# TSAL-S01-V00-Control.net
KiCad netlist of a schematic drawn in Altium Designer
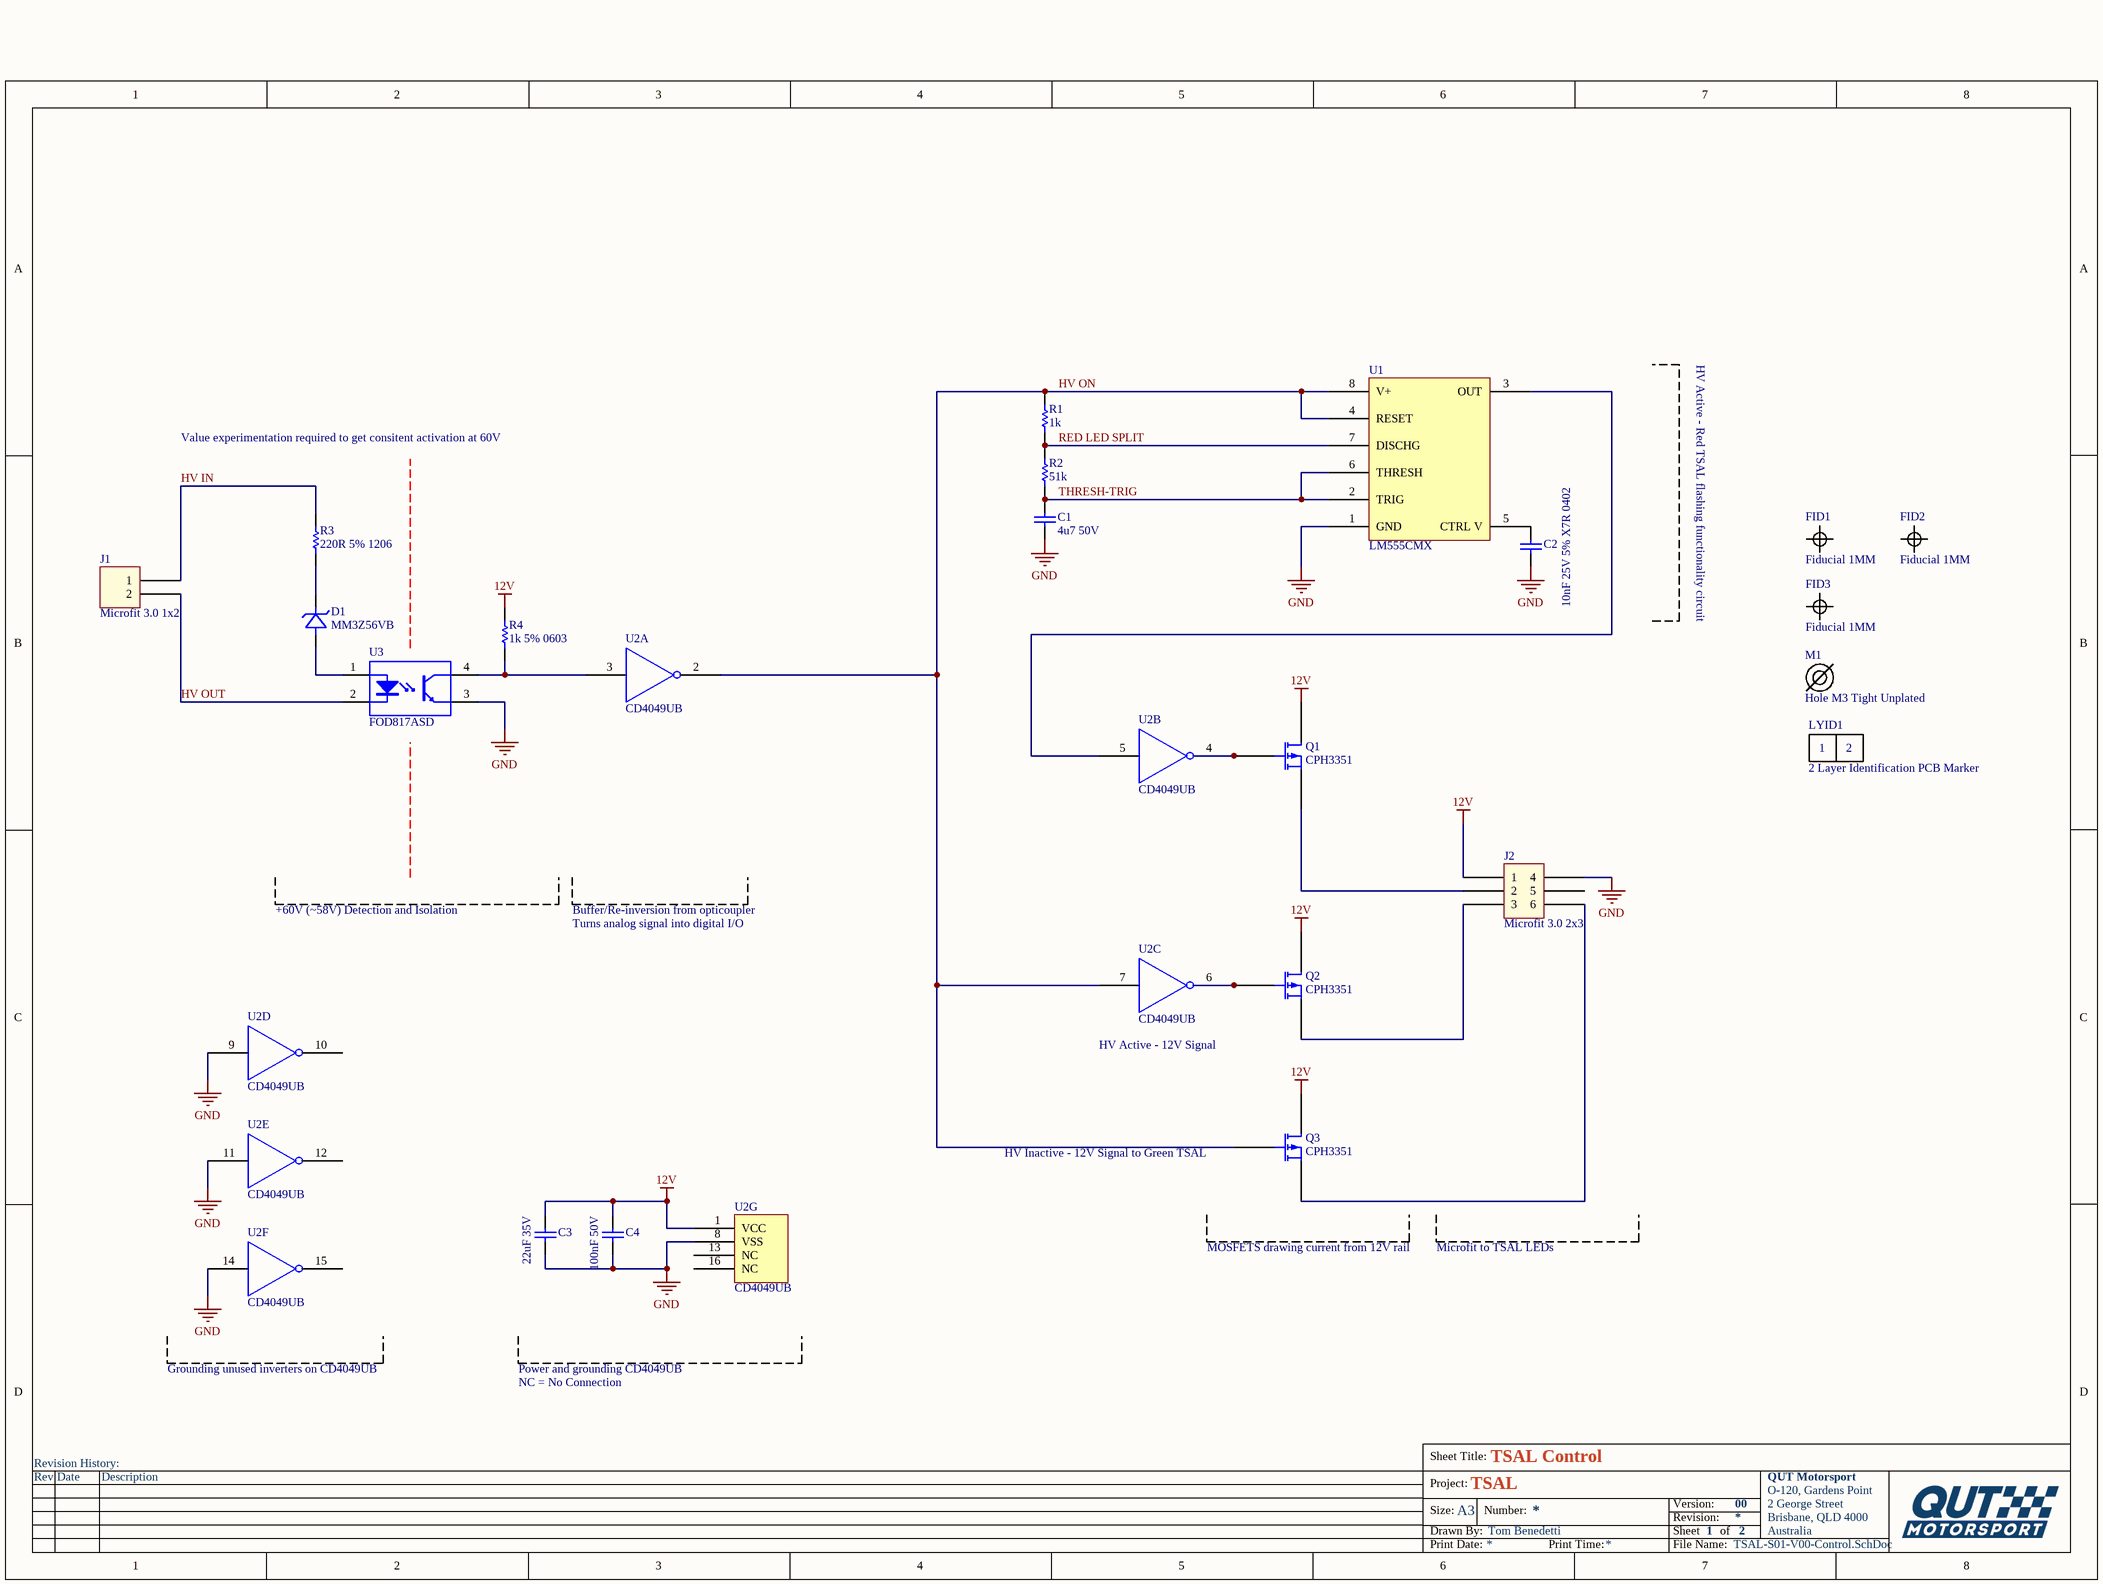
[diagram p0: TSAL-S01-V00-Control.SchDoc]

(export (version "E")
  (design (tool "Eeschema 10.0.6"))
  (components
    (comp (ref "C1")
      (value "4u7 50V")
      (footprint "Cap_Ceramic_0603")
      (description "Capacitor, Ceramic, SMD, 4u7, 50V, 5%, X7R, 0603")
      (libsource (lib "StandardCapacitors") (part "4u7 50V 5% X7R 0603"))
    )
    (comp (ref "C2")
      (value "10nF 25V 5% X7R 0402")
      (footprint "Cap_Ceramic_1206")
      (description "10000pF ±5% 25V Ceramic Capacitor X7R 0402 (1005 Metric)")
      (libsource (lib "StandardCapacitors") (part "10nF 25V 5% X7R 0402"))
    )
    (comp (ref "C3")
      (value "22uF 35V")
      (footprint "Cap_Ceramic_1206")
      (description "22µF ±20% 35V Ceramic Capacitor X5R 1206 (3216 Metric)")
      (libsource (lib "StandardCapacitors") (part "22uF 35V 20% X5R 1206"))
    )
    (comp (ref "C4")
      (value "100nF 50V")
      (footprint "Cap_Ceramic_0603")
      (description "Capacitor, Ceramic, SMD, 100nF, 50V, 5%, X7R, 0603")
      (libsource (lib "StandardCapacitors") (part "100nF 50V 5% X7R 0603"))
    )
    (comp (ref "D1")
      (value "MM3Z56VB")
      (footprint "SOD-323F")
      (description "Zener Diode 56V 200mW ±2% Surface Mount SOD-323F")
      (fields (field (name "MANUFACTURER") "ON Semiconductor"))
      (libsource (lib "QUTMS_DiodeLibrary") (part "MM3Z56VB"))
    )
    (comp (ref "FID1")
      (value "Fiducial 1MM")
      (footprint "FIDUCIAL 1MM")
      (libsource (lib "QUTMS_PCBLibrary") (part "Fiducial 1MM"))
    )
    (comp (ref "FID2")
      (value "Fiducial 1MM")
      (footprint "FIDUCIAL 1MM")
      (libsource (lib "QUTMS_PCBLibrary") (part "Fiducial 1MM"))
    )
    (comp (ref "FID3")
      (value "Fiducial 1MM")
      (footprint "FIDUCIAL 1MM")
      (libsource (lib "QUTMS_PCBLibrary") (part "Fiducial 1MM"))
    )
    (comp (ref "J1")
      (value "Microfit 3.0 1x2")
      (footprint "Microfit_1X2_R_TH")
      (libsource (lib "QUTMS_MicrofitLibrary") (part "Microfit_1x2"))
    )
    (comp (ref "J2")
      (value "Microfit 3.0 2x3")
      (footprint "Microfit_2X3_R_TH")
      (libsource (lib "QUTMS_MicrofitLibrary") (part "Microfit_2x3"))
    )
    (comp (ref "LYID1")
      (value "2 Layer Identification PCB Marker")
      (footprint "LAYER IDENT 2")
      (libsource (lib "QUTMS_PCBLibrary") (part "Layer Identification 2"))
    )
    (comp (ref "M1")
      (value "Hole M3 Tight Unplated")
      (footprint "M3.2 UNPLATED")
      (description "M3.2 Hole, No Plating")
      (libsource (lib "QUTMS_PCBLibrary") (part "Hole M3 Tight Unplated"))
    )
    (comp (ref "Q1")
      (value "CPH3351")
      (footprint "SOT-23-3")
      (description "P-Channel 60V 1.8A (Ta) 1W (Ta) Surface Mount 3-CPH")
      (libsource (lib "QUTMS_Transistors") (part "CPH3351"))
    )
    (comp (ref "Q2")
      (value "CPH3351")
      (footprint "SOT-23-3")
      (description "P-Channel 60V 1.8A (Ta) 1W (Ta) Surface Mount 3-CPH")
      (libsource (lib "QUTMS_Transistors") (part "CPH3351"))
    )
    (comp (ref "Q3")
      (value "CPH3351")
      (footprint "SOT-23-3")
      (description "P-Channel 60V 1.8A (Ta) 1W (Ta) Surface Mount 3-CPH")
      (libsource (lib "QUTMS_Transistors") (part "CPH3351"))
    )
    (comp (ref "R1")
      (value "1k")
      (footprint "Res_ThinFilm_0603")
      (description "Resistor, SMD, 1k, 0.1W, 5%, 0603")
      (libsource (lib "StandardResistors") (part "1k 5% 0603"))
    )
    (comp (ref "R2")
      (value "51k")
      (footprint "Res_ThinFilm_0603")
      (description "51 kOhms ±0.1% 0.063W, 1/16W Chip Resistor 0402 (1005 Metric) Automotive AEC-Q200 Thin Film")
      (libsource (lib "StandardResistors") (part "51k 5% 0603"))
    )
    (comp (ref "R3")
      (value "220R 5% 1206")
      (footprint "Res_ThinFilm_1206")
      (description "220 Ohms ±1% 0.25W, 1/4W Chip Resistor 1206 (3216 Metric) Moisture Resistant Thick Film")
      (libsource (lib "StandardResistors") (part "220R 5% 1206"))
    )
    (comp (ref "R4")
      (value "1k 5% 0603")
      (footprint "Res_ThinFilm_0603")
      (description "Resistor, SMD, 1k, 0.1W, 5%, 0603")
      (libsource (lib "StandardResistors") (part "1k 5% 0603"))
    )
    (comp (ref "U1")
      (value "LM555CMX")
      (footprint "MCP2561 SOIC")
      (description "555 Type, Timer/Oscillator (Single) IC 100kHz 8-SOIC")
      (libsource (lib "QUTMS_IntegratedCircuitLibrary") (part "LM555CMX"))
    )
    (comp (ref "U2")
      (value "CD4049UB")
      (footprint "CD4049UB")
      (libsource (lib "QUTMS_LogicLibrary") (part "CD4049UB"))
    )
    (comp (ref "U3")
      (value "FOD817ASD")
      (footprint "FOD817ASD")
      (description "Optoisolator 5kV Transistor 4SMD")
      (libsource (lib "QUTMS_OctocouplerLibrary") (part "FOD817ASD"))
    )
  )
  (nets
    (net (code "1") (name "/HV IN") (class "Default")
      (node (ref "J1") (pin "1") (pinfunction "1_1") (pintype "passive"))
      (node (ref "R3") (pin "2") (pinfunction "2_2") (pintype "passive"))
    )
    (net (code "2") (name "/HV ON") (class "Default")
      (node (ref "Q3") (pin "G") (pinfunction "G_G") (pintype "passive"))
      (node (ref "R1") (pin "2") (pinfunction "2_2") (pintype "passive"))
      (node (ref "U1") (pin "4") (pinfunction "RESET_4") (pintype "passive"))
      (node (ref "U1") (pin "8") (pinfunction "V+_8") (pintype "passive"))
      (node (ref "U2") (pin "2") (pinfunction "G_2") (pintype "passive"))
      (node (ref "U2") (pin "7") (pinfunction "C_7") (pintype "passive"))
    )
    (net (code "3") (name "/HV OUT") (class "Default")
      (node (ref "J1") (pin "2") (pinfunction "2_2") (pintype "passive"))
      (node (ref "U3") (pin "2") (pinfunction "CATHODE_2") (pintype "passive"))
    )
    (net (code "4") (name "/RED LED SPLIT") (class "Default")
      (node (ref "R1") (pin "1") (pinfunction "1_1") (pintype "passive"))
      (node (ref "R2") (pin "2") (pinfunction "2_2") (pintype "passive"))
      (node (ref "U1") (pin "7") (pinfunction "DISCHG_7") (pintype "passive"))
    )
    (net (code "5") (name "/THRESH-TRIG") (class "Default")
      (node (ref "C1") (pin "2") (pinfunction "2_2") (pintype "passive"))
      (node (ref "R2") (pin "1") (pinfunction "1_1") (pintype "passive"))
      (node (ref "U1") (pin "2") (pinfunction "TRIG_2") (pintype "passive"))
      (node (ref "U1") (pin "6") (pinfunction "THRESH_6") (pintype "passive"))
    )
    (net (code "6") (name "12V") (class "Default")
      (node (ref "C3") (pin "2") (pinfunction "2_2") (pintype "passive"))
      (node (ref "C4") (pin "2") (pinfunction "2_2") (pintype "passive"))
      (node (ref "J2") (pin "1") (pinfunction "1_1") (pintype "passive"))
      (node (ref "Q1") (pin "D") (pinfunction "D_D") (pintype "passive"))
      (node (ref "Q2") (pin "D") (pinfunction "D_D") (pintype "passive"))
      (node (ref "Q3") (pin "D") (pinfunction "D_D") (pintype "passive"))
      (node (ref "R4") (pin "2") (pinfunction "2_2") (pintype "passive"))
      (node (ref "U2") (pin "1") (pinfunction "VCC_1") (pintype "passive"))
    )
    (net (code "7") (name "GND") (class "Default")
      (node (ref "C1") (pin "1") (pinfunction "1_1") (pintype "passive"))
      (node (ref "C2") (pin "1") (pinfunction "1_1") (pintype "passive"))
      (node (ref "C3") (pin "1") (pinfunction "1_1") (pintype "passive"))
      (node (ref "C4") (pin "1") (pinfunction "1_1") (pintype "passive"))
      (node (ref "J2") (pin "4") (pinfunction "4_4") (pintype "passive"))
      (node (ref "U1") (pin "1") (pinfunction "GND_1") (pintype "passive"))
      (node (ref "U2") (pin "11") (pinfunction "E_11") (pintype "passive"))
      (node (ref "U2") (pin "14") (pinfunction "F_14") (pintype "passive"))
      (node (ref "U2") (pin "8") (pinfunction "VSS_8") (pintype "passive"))
      (node (ref "U2") (pin "9") (pinfunction "D_9") (pintype "passive"))
      (node (ref "U3") (pin "3") (pinfunction "EMITTER_3") (pintype "passive"))
    )
    (net (code "8") (name "Net-(D1-Anode)") (class "Default")
      (node (ref "D1") (pin "1") (pinfunction "Anode_1") (pintype "passive"))
      (node (ref "U3") (pin "1") (pinfunction "ANODE_1") (pintype "passive"))
    )
    (net (code "9") (name "Net-(D1-Cathode)") (class "Default")
      (node (ref "D1") (pin "2") (pinfunction "Cathode_2") (pintype "passive"))
      (node (ref "R3") (pin "1") (pinfunction "1_1") (pintype "passive"))
    )
    (net (code "10") (name "Net-(J2-Pad2)") (class "Default")
      (node (ref "J2") (pin "2") (pinfunction "2_2") (pintype "passive"))
      (node (ref "Q1") (pin "S") (pinfunction "S_S") (pintype "passive"))
    )
    (net (code "11") (name "Net-(J2-Pad3)") (class "Default")
      (node (ref "J2") (pin "3") (pinfunction "3_3") (pintype "passive"))
      (node (ref "Q2") (pin "S") (pinfunction "S_S") (pintype "passive"))
    )
    (net (code "12") (name "Net-(J2-Pad6)") (class "Default")
      (node (ref "J2") (pin "6") (pinfunction "6_6") (pintype "passive"))
      (node (ref "Q3") (pin "S") (pinfunction "S_S") (pintype "passive"))
    )
    (net (code "13") (name "Net-(U1-CTRL_V)") (class "Default")
      (node (ref "C2") (pin "2") (pinfunction "2_2") (pintype "passive"))
      (node (ref "U1") (pin "5") (pinfunction "CTRL_V_5") (pintype "passive"))
    )
    (net (code "14") (name "Net-(U1-OUT)") (class "Default")
      (node (ref "U1") (pin "3") (pinfunction "OUT_3") (pintype "passive"))
      (node (ref "U2") (pin "5") (pinfunction "B_5") (pintype "passive"))
    )
    (net (code "15") (name "Net-(U2A-A)") (class "Default")
      (node (ref "R4") (pin "1") (pinfunction "1_1") (pintype "passive"))
      (node (ref "U2") (pin "3") (pinfunction "A_3") (pintype "passive"))
      (node (ref "U3") (pin "4") (pinfunction "COLLECTOR_4") (pintype "passive"))
    )
    (net (code "16") (name "Net-(U2B-H)") (class "Default")
      (node (ref "Q1") (pin "G") (pinfunction "G_G") (pintype "passive"))
      (node (ref "U2") (pin "4") (pinfunction "H_4") (pintype "passive"))
    )
    (net (code "17") (name "Net-(U2C-I)") (class "Default")
      (node (ref "Q2") (pin "G") (pinfunction "G_G") (pintype "passive"))
      (node (ref "U2") (pin "6") (pinfunction "I_6") (pintype "passive"))
    )
    (net (code "18") (name "unconnected-(J2-Pad5)") (class "Default")
      (node (ref "J2") (pin "5") (pinfunction "5_5") (pintype "passive"))
    )
    (net (code "19") (name "unconnected-(U2D-J-Pad10)") (class "Default")
      (node (ref "U2") (pin "10") (pinfunction "J_10") (pintype "passive"))
    )
    (net (code "20") (name "unconnected-(U2E-K-Pad12)") (class "Default")
      (node (ref "U2") (pin "12") (pinfunction "K_12") (pintype "passive"))
    )
    (net (code "21") (name "unconnected-(U2F-L-Pad15)") (class "Default")
      (node (ref "U2") (pin "15") (pinfunction "L_15") (pintype "passive"))
    )
    (net (code "22") (name "unconnected-(U2G-NC-Pad13)") (class "Default")
      (node (ref "U2") (pin "13") (pinfunction "NC_13") (pintype "passive"))
    )
    (net (code "23") (name "unconnected-(U2G-NC-Pad16)") (class "Default")
      (node (ref "U2") (pin "16") (pinfunction "NC_16") (pintype "passive"))
    )
  )
)
